# tvp3.net
KiCad netlist of a schematic drawn in EAGLE
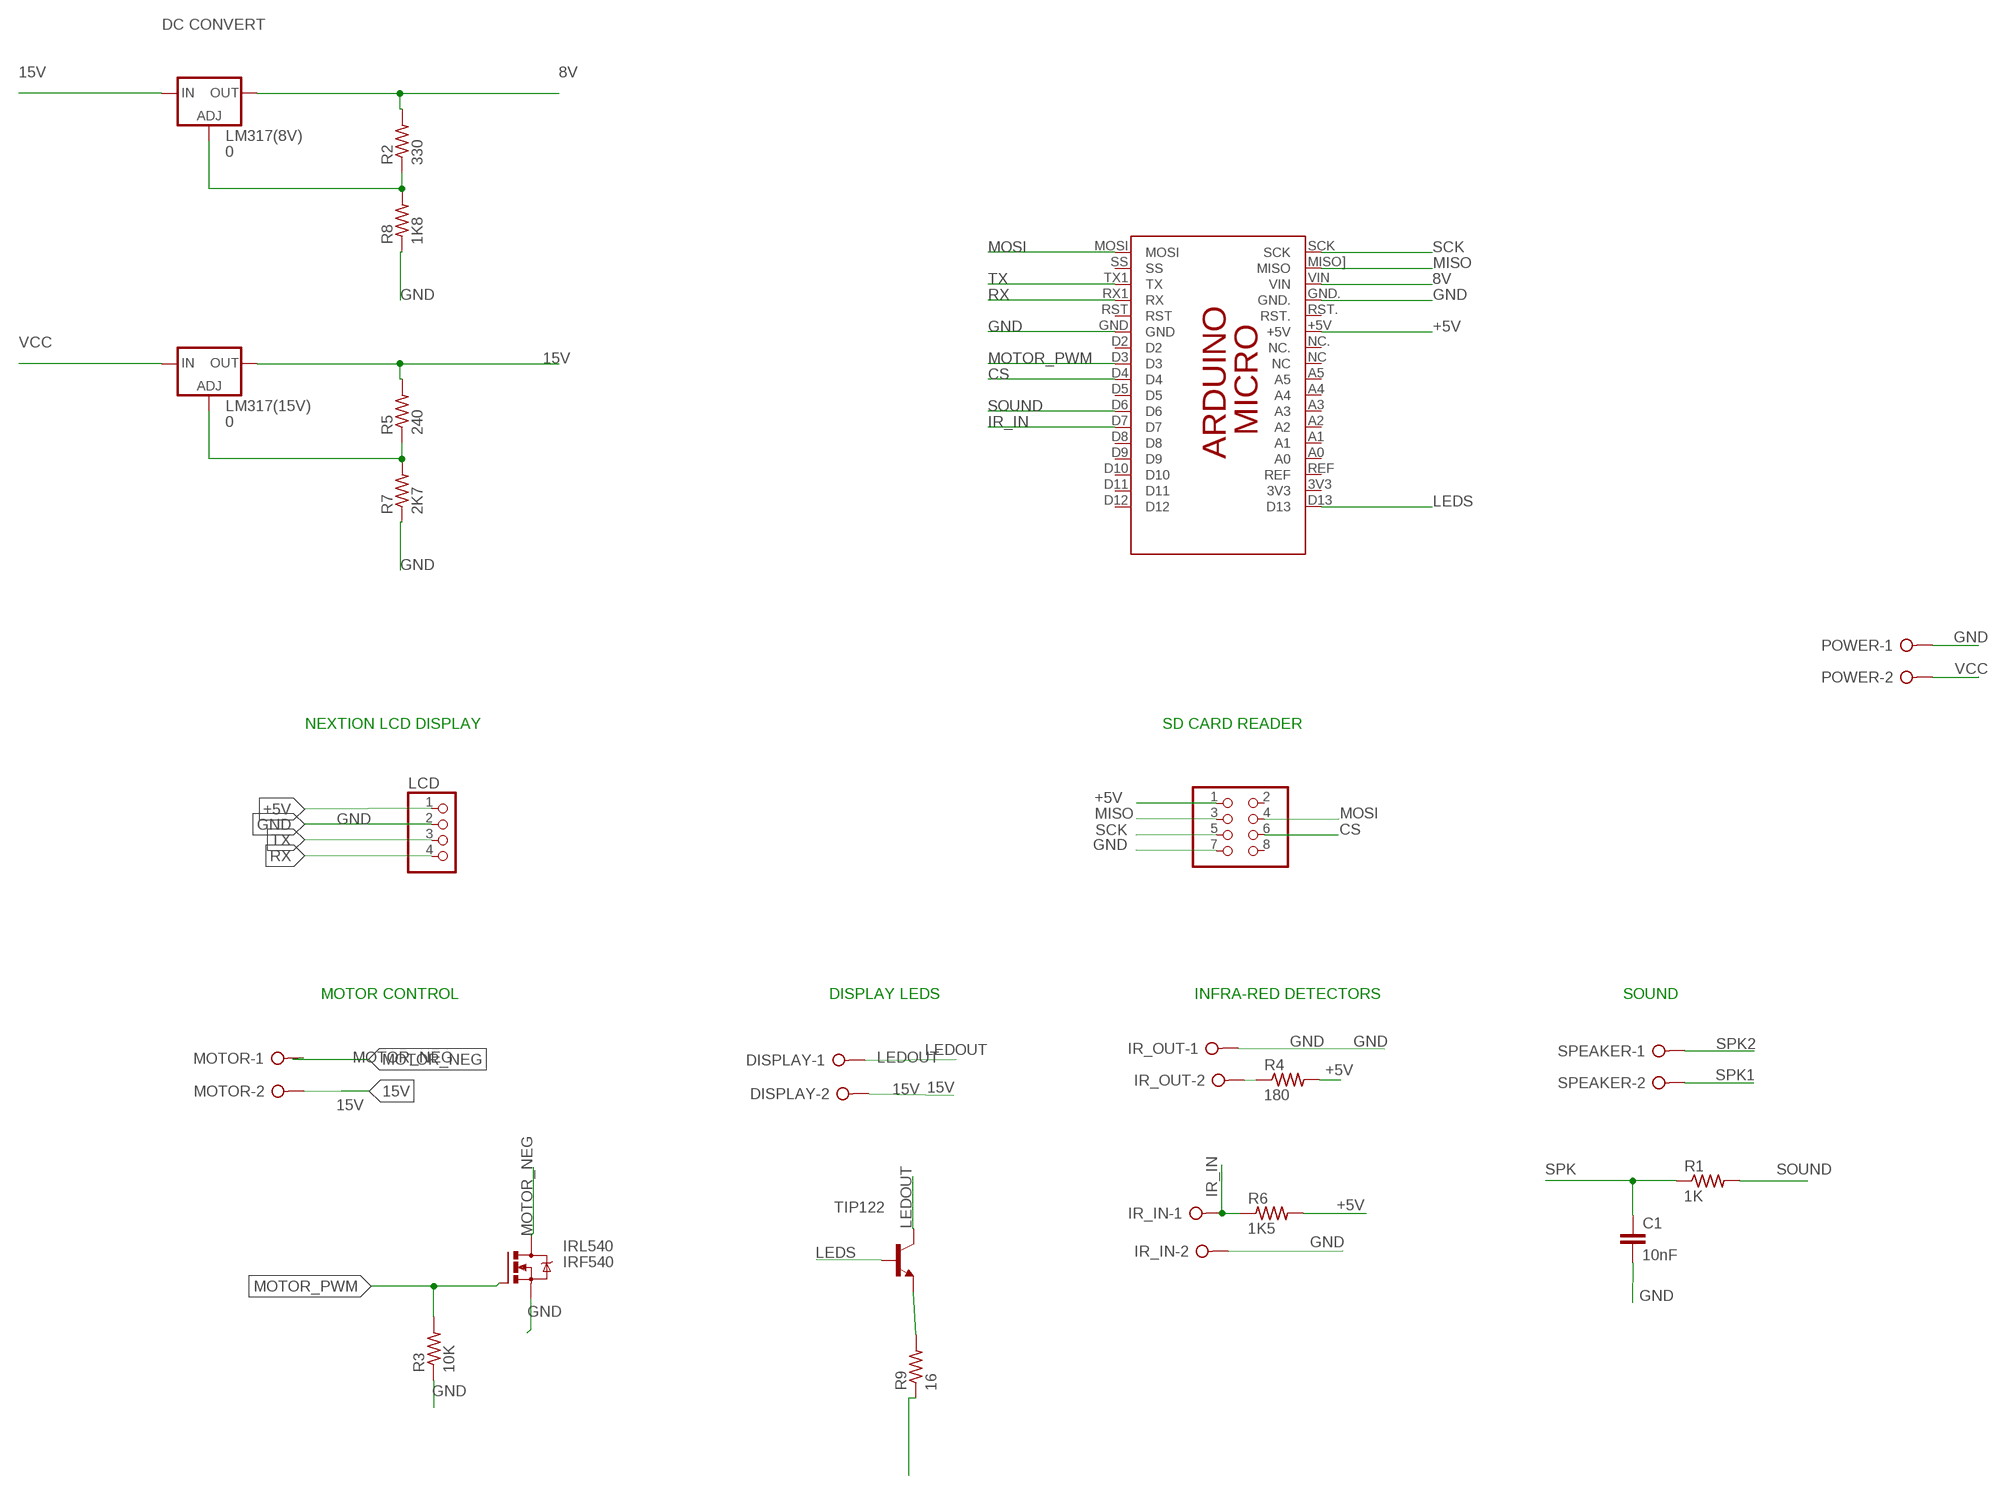
[diagram p0: schematic, sheet 1]
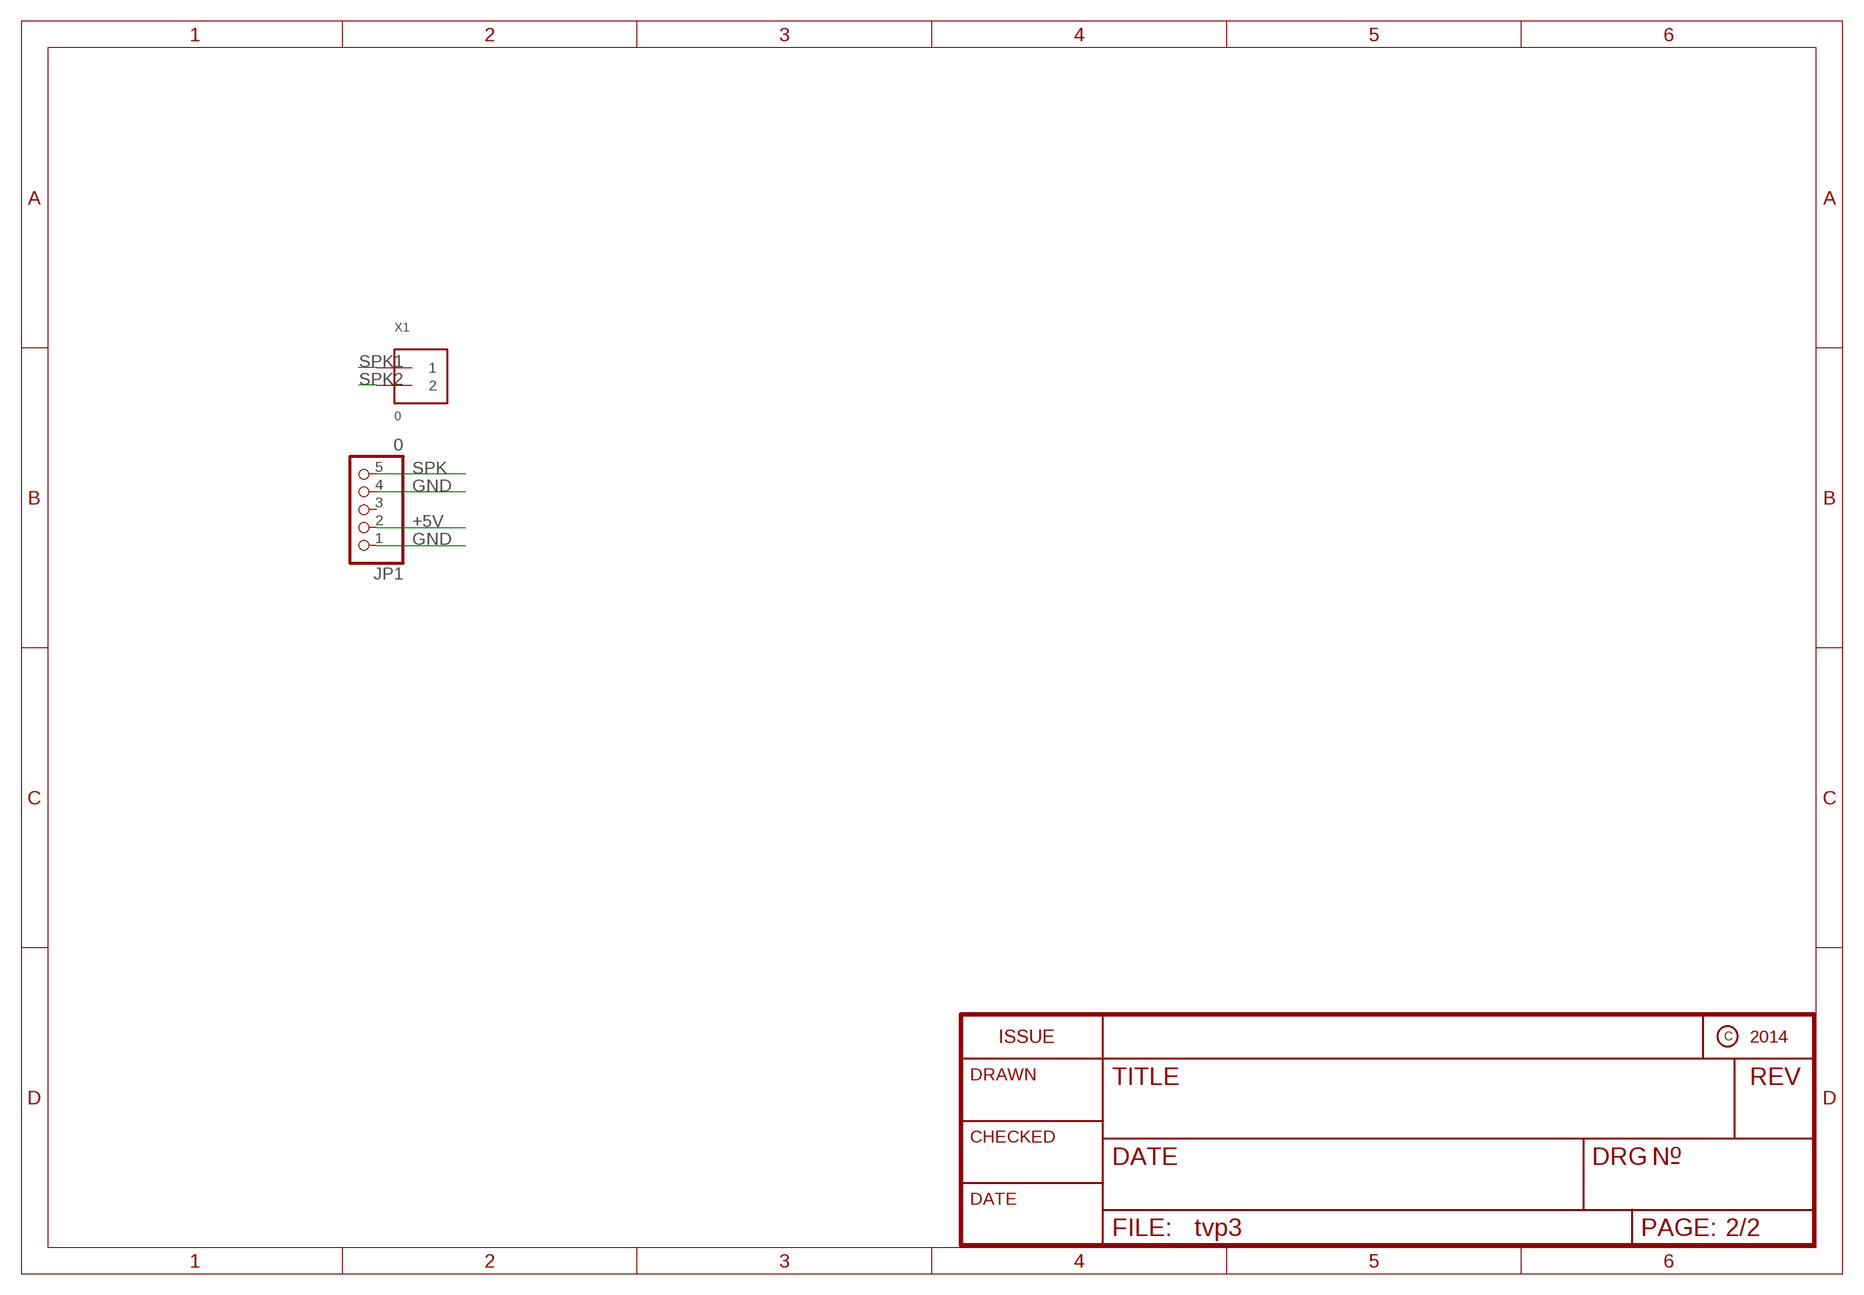
[diagram p1: schematic, sheet 2]

(export (version "E")
  (design (tool "Eeschema 10.0.6"))
  (components
    (comp (ref "JP1")
      (value "0")
      (footprint "eagle-import:1X05_ROUND_70")
      (libsource (lib "eagle-import") (part "HEADER-1X570MIL"))
    )
    (comp (ref "X1")
      (value "0")
      (footprint "eagle-import:TERMBLOCK_1X2-3.5MM")
      (libsource (lib "eagle-import") (part "TERMBLOCK_1X2"))
    )
    (comp (ref "C1")
      (value "10nF")
      (footprint "eagle-import:C2.5-2")
      (libsource (lib "eagle-import") (part "C2.5/2"))
    )
    (comp (ref "DISPLAY")
      (value "W237-02P")
      (footprint "eagle-import:W237-132")
      (libsource (lib "eagle-import") (part "W237-02P"))
    )
    (comp (ref "IRL540")
      (value "IRF540")
      (footprint "eagle-import:TO220BV")
      (libsource (lib "eagle-import") (part "IRF540"))
    )
    (comp (ref "IR_IN")
      (value "W237-02P")
      (footprint "eagle-import:W237-132")
      (libsource (lib "eagle-import") (part "W237-02P"))
    )
    (comp (ref "IR_OUT")
      (value "W237-02P")
      (footprint "eagle-import:W237-132")
      (libsource (lib "eagle-import") (part "W237-02P"))
    )
    (comp (ref "LCD")
      (value "PINHD-1X4")
      (footprint "eagle-import:1X04")
      (libsource (lib "eagle-import") (part "PINHD-1X4"))
    )
    (comp (ref "LM317(8V)")
      (value "0")
      (footprint "eagle-import:317TS")
      (libsource (lib "eagle-import") (part "LM317TS"))
    )
    (comp (ref "LM317(15V)")
      (value "0")
      (footprint "eagle-import:317TS")
      (libsource (lib "eagle-import") (part "LM317TS"))
    )
    (comp (ref "MOTOR")
      (value "W237-02P")
      (footprint "eagle-import:W237-132")
      (libsource (lib "eagle-import") (part "W237-02P"))
    )
    (comp (ref "PCB2")
      (value "ARDUINO_MICRO")
      (footprint "eagle-import:ARDUINO_MICRO")
      (libsource (lib "eagle-import") (part "ARDUINO_MICRO"))
    )
    (comp (ref "POWER")
      (value "W237-02P")
      (footprint "eagle-import:W237-132")
      (libsource (lib "eagle-import") (part "W237-02P"))
    )
    (comp (ref "R1")
      (value "1K")
      (footprint "eagle-import:0207_10")
      (libsource (lib "eagle-import") (part "R-US_0207/10"))
    )
    (comp (ref "R2")
      (value "330")
      (footprint "eagle-import:0207_10")
      (libsource (lib "eagle-import") (part "R-US_0207/10"))
    )
    (comp (ref "R3")
      (value "10K")
      (footprint "eagle-import:0207_10")
      (libsource (lib "eagle-import") (part "R-US_0207/10"))
    )
    (comp (ref "R4")
      (value "180")
      (footprint "eagle-import:0207_10")
      (libsource (lib "eagle-import") (part "R-US_0207/10"))
    )
    (comp (ref "R5")
      (value "240")
      (footprint "eagle-import:0207_10")
      (libsource (lib "eagle-import") (part "R-US_0207/10"))
    )
    (comp (ref "R6")
      (value "1K5")
      (footprint "eagle-import:0207_10")
      (libsource (lib "eagle-import") (part "R-US_0207/10"))
    )
    (comp (ref "R7")
      (value "2K7")
      (footprint "eagle-import:0207_10")
      (libsource (lib "eagle-import") (part "R-US_0207/10"))
    )
    (comp (ref "R8")
      (value "1K8")
      (footprint "eagle-import:0207_10")
      (libsource (lib "eagle-import") (part "R-US_0207/10"))
    )
    (comp (ref "R9")
      (value "16")
      (footprint "eagle-import:0207_10")
      (libsource (lib "eagle-import") (part "R-US_0207/10"))
    )
    (comp (ref "SPEAKER")
      (value "W237-02P")
      (footprint "eagle-import:W237-132")
      (libsource (lib "eagle-import") (part "W237-02P"))
    )
    (comp (ref "TIP122")
      (value "-NPN-TO220V")
      (footprint "eagle-import:TO220V")
      (libsource (lib "eagle-import") (part "-NPN-TO220V"))
    )
    (comp (ref "_")
      (value "PINHD-2X4")
      (footprint "eagle-import:2X04")
      (libsource (lib "eagle-import") (part "PINHD-2X4"))
    )
  )
  (nets
    (net (code "1") (name "+5V") (class "Default")
      (node (ref "JP1") (pin "2") (pinfunction "2_2") (pintype "passive"))
      (node (ref "LCD") (pin "1") (pinfunction "1_1") (pintype "passive"))
      (node (ref "PCB2") (pin "+5V") (pinfunction "+5V_+5V") (pintype "bidirectional"))
      (node (ref "R4") (pin "2") (pinfunction "2_2") (pintype "passive"))
      (node (ref "R6") (pin "2") (pinfunction "2_2") (pintype "passive"))
      (node (ref "_") (pin "1") (pinfunction "1_1") (pintype "passive"))
    )
    (net (code "2") (name "8V") (class "Default")
      (node (ref "LM317(8V)") (pin "2") (pinfunction "OUT_2") (pintype "passive"))
      (node (ref "PCB2") (pin "VIN") (pinfunction "VIN_VIN") (pintype "bidirectional"))
      (node (ref "R2") (pin "2") (pinfunction "2_2") (pintype "passive"))
    )
    (net (code "3") (name "15V") (class "Default")
      (node (ref "DISPLAY") (pin "2") (pinfunction "KL_2") (pintype "passive"))
      (node (ref "LM317(15V)") (pin "2") (pinfunction "OUT_2") (pintype "passive"))
      (node (ref "LM317(8V)") (pin "3") (pinfunction "IN_3") (pintype "input"))
      (node (ref "MOTOR") (pin "2") (pinfunction "KL_2") (pintype "passive"))
      (node (ref "R5") (pin "2") (pinfunction "2_2") (pintype "passive"))
    )
    (net (code "4") (name "CS") (class "Default")
      (node (ref "PCB2") (pin "D4") (pinfunction "D4_D4") (pintype "bidirectional"))
      (node (ref "_") (pin "6") (pinfunction "6_6") (pintype "passive"))
    )
    (net (code "5") (name "GND") (class "Default")
      (node (ref "C1") (pin "2") (pinfunction "2_2") (pintype "passive"))
      (node (ref "IRL540") (pin "S") (pinfunction "S_S") (pintype "passive"))
      (node (ref "IR_IN") (pin "2") (pinfunction "KL_2") (pintype "passive"))
      (node (ref "IR_OUT") (pin "1") (pinfunction "KL_1") (pintype "passive"))
      (node (ref "JP1") (pin "1") (pinfunction "1_1") (pintype "passive"))
      (node (ref "JP1") (pin "4") (pinfunction "4_4") (pintype "passive"))
      (node (ref "LCD") (pin "2") (pinfunction "2_2") (pintype "passive"))
      (node (ref "PCB2") (pin "GND") (pinfunction "GND_GND") (pintype "bidirectional"))
      (node (ref "PCB2") (pin "GND.") (pinfunction "GND._GND.") (pintype "bidirectional"))
      (node (ref "POWER") (pin "1") (pinfunction "KL_1") (pintype "passive"))
      (node (ref "R3") (pin "1") (pinfunction "1_1") (pintype "passive"))
      (node (ref "R7") (pin "1") (pinfunction "1_1") (pintype "passive"))
      (node (ref "R8") (pin "1") (pinfunction "1_1") (pintype "passive"))
      (node (ref "R9") (pin "1") (pinfunction "1_1") (pintype "passive"))
      (node (ref "_") (pin "7") (pinfunction "7_7") (pintype "passive"))
    )
    (net (code "6") (name "IR_IN") (class "Default")
      (node (ref "IR_IN") (pin "1") (pinfunction "KL_1") (pintype "passive"))
      (node (ref "PCB2") (pin "D7") (pinfunction "D7_D7") (pintype "bidirectional"))
      (node (ref "R6") (pin "1") (pinfunction "1_1") (pintype "passive"))
    )
    (net (code "7") (name "LEDOUT") (class "Default")
      (node (ref "DISPLAY") (pin "1") (pinfunction "KL_1") (pintype "passive"))
      (node (ref "TIP122") (pin "2") (pinfunction "C_2") (pintype "passive"))
    )
    (net (code "8") (name "LEDS") (class "Default")
      (node (ref "PCB2") (pin "D13") (pinfunction "D13_D13") (pintype "bidirectional"))
      (node (ref "TIP122") (pin "1") (pinfunction "B_1") (pintype "passive"))
    )
    (net (code "9") (name "MISO") (class "Default")
      (node (ref "PCB2") (pin "MISO]") (pinfunction "MISO_MISO]") (pintype "bidirectional"))
      (node (ref "_") (pin "3") (pinfunction "3_3") (pintype "passive"))
    )
    (net (code "10") (name "MOSI") (class "Default")
      (node (ref "PCB2") (pin "MOSI") (pinfunction "MOSI_MOSI") (pintype "bidirectional"))
      (node (ref "_") (pin "4") (pinfunction "4_4") (pintype "passive"))
    )
    (net (code "11") (name "MOTOR_NEG") (class "Default")
      (node (ref "IRL540") (pin "D") (pinfunction "D_D") (pintype "passive"))
      (node (ref "MOTOR") (pin "1") (pinfunction "KL_1") (pintype "passive"))
    )
    (net (code "12") (name "MOTOR_PWM") (class "Default")
      (node (ref "IRL540") (pin "G") (pinfunction "G_G") (pintype "passive"))
      (node (ref "PCB2") (pin "D3") (pinfunction "D3_D3") (pintype "bidirectional"))
      (node (ref "R3") (pin "2") (pinfunction "2_2") (pintype "passive"))
    )
    (net (code "13") (name "Net-(IR_OUTB-KL)") (class "Default")
      (node (ref "IR_OUT") (pin "2") (pinfunction "KL_2") (pintype "passive"))
      (node (ref "R4") (pin "1") (pinfunction "1_1") (pintype "passive"))
    )
    (net (code "14") (name "Net-(LM317(8V)-ADJ)") (class "Default")
      (node (ref "LM317(8V)") (pin "1") (pinfunction "ADJ_1") (pintype "input"))
      (node (ref "R2") (pin "1") (pinfunction "1_1") (pintype "passive"))
      (node (ref "R8") (pin "2") (pinfunction "2_2") (pintype "passive"))
    )
    (net (code "15") (name "Net-(LM317(15V)-ADJ)") (class "Default")
      (node (ref "LM317(15V)") (pin "1") (pinfunction "ADJ_1") (pintype "input"))
      (node (ref "R5") (pin "1") (pinfunction "1_1") (pintype "passive"))
      (node (ref "R7") (pin "2") (pinfunction "2_2") (pintype "passive"))
    )
    (net (code "16") (name "Net-(TIP122-E)") (class "Default")
      (node (ref "R9") (pin "2") (pinfunction "2_2") (pintype "passive"))
      (node (ref "TIP122") (pin "3") (pinfunction "E_3") (pintype "passive"))
    )
    (net (code "17") (name "RX") (class "Default")
      (node (ref "LCD") (pin "4") (pinfunction "4_4") (pintype "passive"))
      (node (ref "PCB2") (pin "RX1") (pinfunction "RX_RX1") (pintype "bidirectional"))
    )
    (net (code "18") (name "SCK") (class "Default")
      (node (ref "PCB2") (pin "SCK") (pinfunction "SCK_SCK") (pintype "bidirectional"))
      (node (ref "_") (pin "5") (pinfunction "5_5") (pintype "passive"))
    )
    (net (code "19") (name "SOUND") (class "Default")
      (node (ref "PCB2") (pin "D6") (pinfunction "D6_D6") (pintype "bidirectional"))
      (node (ref "R1") (pin "2") (pinfunction "2_2") (pintype "passive"))
    )
    (net (code "20") (name "SPK") (class "Default")
      (node (ref "C1") (pin "1") (pinfunction "1_1") (pintype "passive"))
      (node (ref "JP1") (pin "5") (pinfunction "5_5") (pintype "passive"))
      (node (ref "R1") (pin "1") (pinfunction "1_1") (pintype "passive"))
    )
    (net (code "21") (name "SPK1") (class "Default")
      (node (ref "SPEAKER") (pin "2") (pinfunction "KL_2") (pintype "passive"))
      (node (ref "X1") (pin "1") (pinfunction "1_1") (pintype "passive"))
    )
    (net (code "22") (name "SPK2") (class "Default")
      (node (ref "SPEAKER") (pin "1") (pinfunction "KL_1") (pintype "passive"))
      (node (ref "X1") (pin "2") (pinfunction "2_2") (pintype "passive"))
    )
    (net (code "23") (name "TX") (class "Default")
      (node (ref "LCD") (pin "3") (pinfunction "3_3") (pintype "passive"))
      (node (ref "PCB2") (pin "TX1") (pinfunction "TX_TX1") (pintype "bidirectional"))
    )
    (net (code "24") (name "VCC") (class "Default")
      (node (ref "LM317(15V)") (pin "3") (pinfunction "IN_3") (pintype "input"))
      (node (ref "POWER") (pin "2") (pinfunction "KL_2") (pintype "passive"))
    )
    (net (code "25") (name "unconnected-(JP1-Pad3)") (class "Default")
      (node (ref "JP1") (pin "3") (pinfunction "3_3") (pintype "passive"))
    )
    (net (code "26") (name "unconnected-(PCB2-Pad3V3)") (class "Default")
      (node (ref "PCB2") (pin "3V3") (pinfunction "3V3_3V3") (pintype "bidirectional"))
    )
    (net (code "27") (name "unconnected-(PCB2-PadA0)") (class "Default")
      (node (ref "PCB2") (pin "A0") (pinfunction "A0_A0") (pintype "bidirectional"))
    )
    (net (code "28") (name "unconnected-(PCB2-PadA1)") (class "Default")
      (node (ref "PCB2") (pin "A1") (pinfunction "A1_A1") (pintype "bidirectional"))
    )
    (net (code "29") (name "unconnected-(PCB2-PadA2)") (class "Default")
      (node (ref "PCB2") (pin "A2") (pinfunction "A2_A2") (pintype "bidirectional"))
    )
    (net (code "30") (name "unconnected-(PCB2-PadA3)") (class "Default")
      (node (ref "PCB2") (pin "A3") (pinfunction "A3_A3") (pintype "bidirectional"))
    )
    (net (code "31") (name "unconnected-(PCB2-PadA4)") (class "Default")
      (node (ref "PCB2") (pin "A4") (pinfunction "A4_A4") (pintype "bidirectional"))
    )
    (net (code "32") (name "unconnected-(PCB2-PadA5)") (class "Default")
      (node (ref "PCB2") (pin "A5") (pinfunction "A5_A5") (pintype "bidirectional"))
    )
    (net (code "33") (name "unconnected-(PCB2-PadD2)") (class "Default")
      (node (ref "PCB2") (pin "D2") (pinfunction "D2_D2") (pintype "bidirectional"))
    )
    (net (code "34") (name "unconnected-(PCB2-PadD5)") (class "Default")
      (node (ref "PCB2") (pin "D5") (pinfunction "D5_D5") (pintype "bidirectional"))
    )
    (net (code "35") (name "unconnected-(PCB2-PadD8)") (class "Default")
      (node (ref "PCB2") (pin "D8") (pinfunction "D8_D8") (pintype "bidirectional"))
    )
    (net (code "36") (name "unconnected-(PCB2-PadD9)") (class "Default")
      (node (ref "PCB2") (pin "D9") (pinfunction "D9_D9") (pintype "bidirectional"))
    )
    (net (code "37") (name "unconnected-(PCB2-PadD10)") (class "Default")
      (node (ref "PCB2") (pin "D10") (pinfunction "D10_D10") (pintype "bidirectional"))
    )
    (net (code "38") (name "unconnected-(PCB2-PadD11)") (class "Default")
      (node (ref "PCB2") (pin "D11") (pinfunction "D11_D11") (pintype "bidirectional"))
    )
    (net (code "39") (name "unconnected-(PCB2-PadD12)") (class "Default")
      (node (ref "PCB2") (pin "D12") (pinfunction "D12_D12") (pintype "bidirectional"))
    )
    (net (code "40") (name "unconnected-(PCB2-PadNC)") (class "Default")
      (node (ref "PCB2") (pin "NC") (pinfunction "NC_NC") (pintype "bidirectional"))
    )
    (net (code "41") (name "unconnected-(PCB2-PadNC.)") (class "Default")
      (node (ref "PCB2") (pin "NC.") (pinfunction "NC._NC.") (pintype "bidirectional"))
    )
    (net (code "42") (name "unconnected-(PCB2-PadREF)") (class "Default")
      (node (ref "PCB2") (pin "REF") (pinfunction "REF_REF") (pintype "bidirectional"))
    )
    (net (code "43") (name "unconnected-(PCB2-PadRST)") (class "Default")
      (node (ref "PCB2") (pin "RST") (pinfunction "RST_RST") (pintype "bidirectional"))
    )
    (net (code "44") (name "unconnected-(PCB2-PadRST.)") (class "Default")
      (node (ref "PCB2") (pin "RST.") (pinfunction "RST._RST.") (pintype "bidirectional"))
    )
    (net (code "45") (name "unconnected-(PCB2-PadSS)") (class "Default")
      (node (ref "PCB2") (pin "SS") (pinfunction "SS_SS") (pintype "bidirectional"))
    )
    (net (code "46") (name "unconnected-(_-Pad2)") (class "Default")
      (node (ref "_") (pin "2") (pinfunction "2_2") (pintype "passive"))
    )
    (net (code "47") (name "unconnected-(_-Pad8)") (class "Default")
      (node (ref "_") (pin "8") (pinfunction "8_8") (pintype "passive"))
    )
  )
)
